# motor_driver.net
KiCad netlist of a schematic drawn in EAGLE
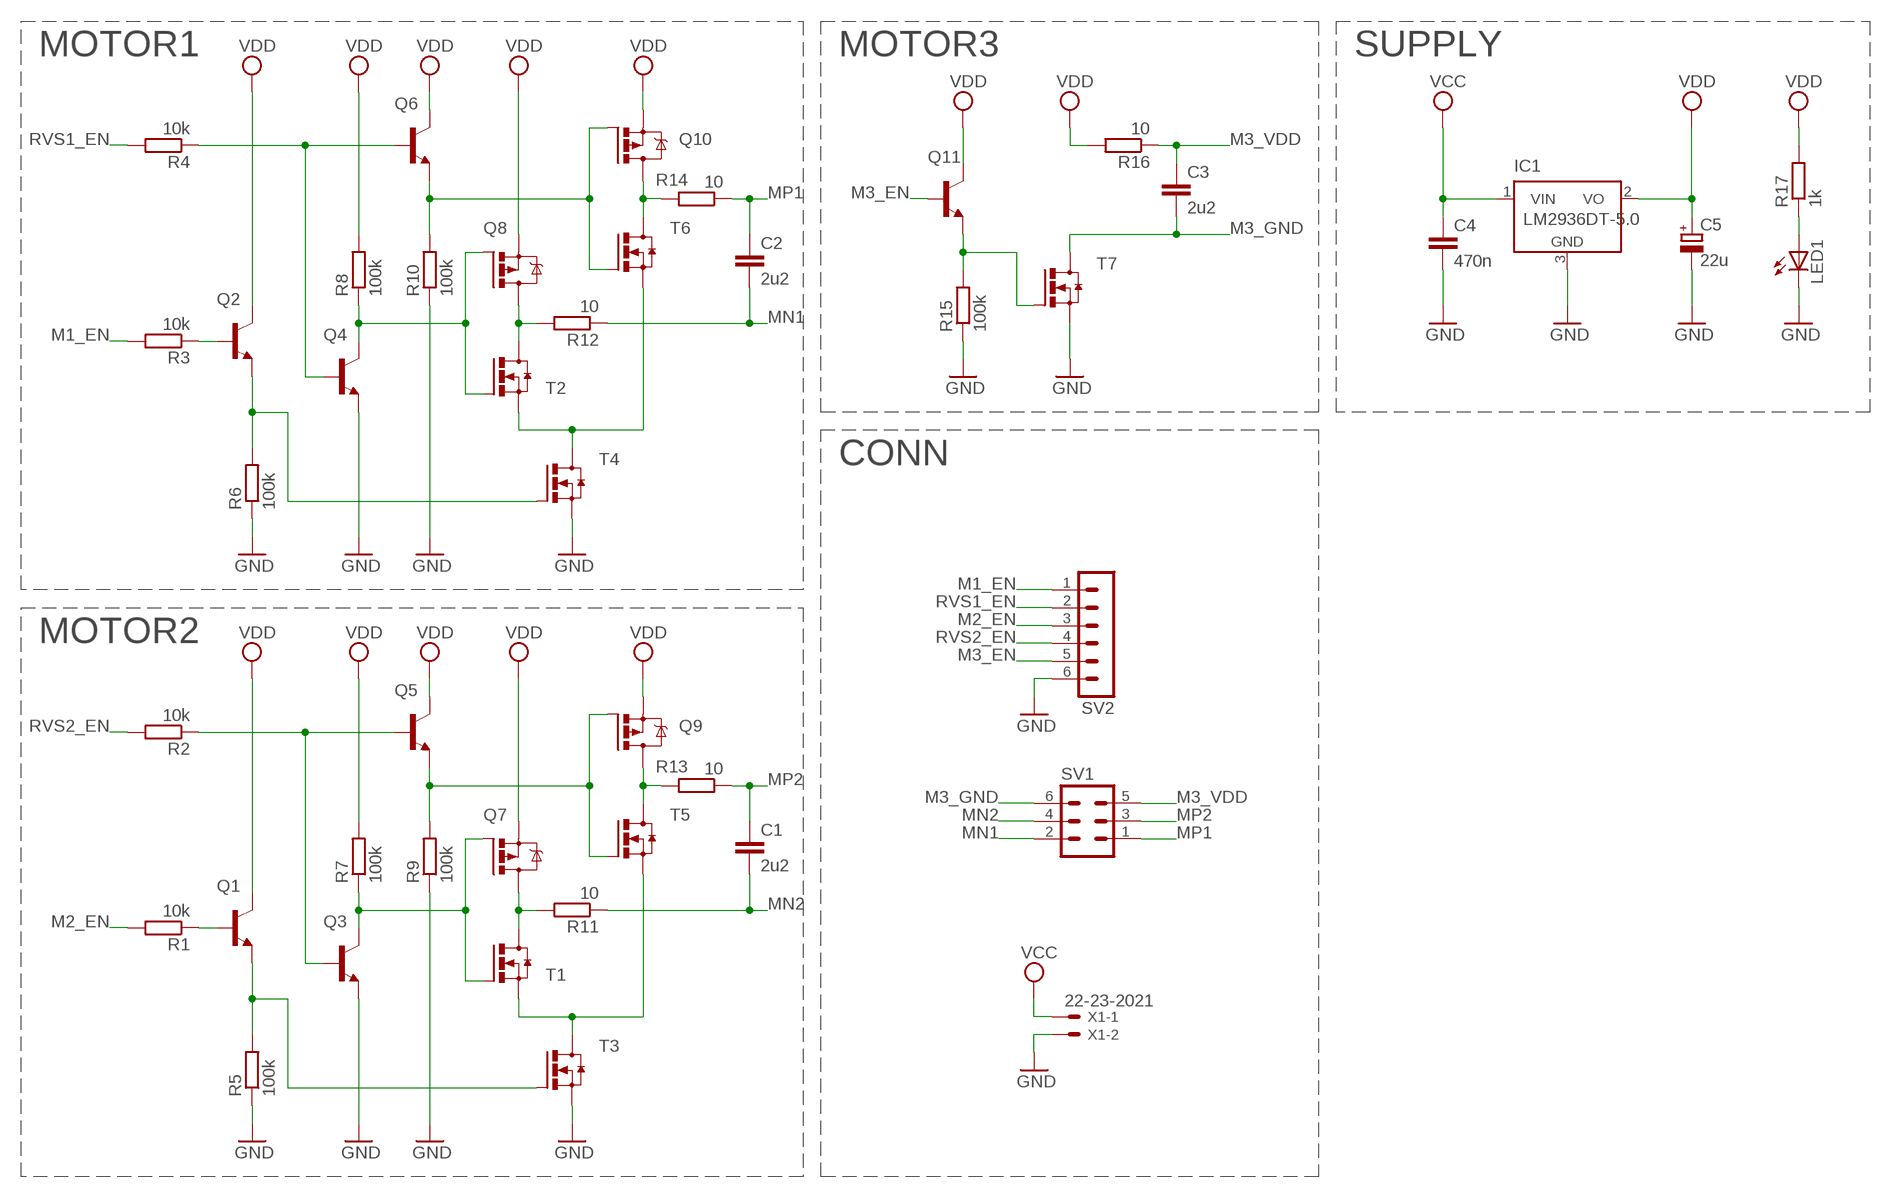
[diagram p0: schematic, sheet 1]

(export (version "E")
  (design (tool "Eeschema 10.0.6"))
  (components
    (comp (ref "C1")
      (value "2u2")
      (footprint "eagle-import:C025-025X050")
      (libsource (lib "eagle-import") (part "C-EU025-025X050"))
    )
    (comp (ref "C2")
      (value "2u2")
      (footprint "eagle-import:C025-025X050")
      (libsource (lib "eagle-import") (part "C-EU025-025X050"))
    )
    (comp (ref "C3")
      (value "2u2")
      (footprint "eagle-import:C025-025X050")
      (libsource (lib "eagle-import") (part "C-EU025-025X050"))
    )
    (comp (ref "C4")
      (value "470n")
      (footprint "eagle-import:C0805")
      (libsource (lib "eagle-import") (part "C-EUC0805"))
    )
    (comp (ref "C5")
      (value "22u")
      (footprint "eagle-import:150CLZ-1014")
      (libsource (lib "eagle-import") (part "CPOL-EU150CLZ-1014"))
    )
    (comp (ref "IC1")
      (value "LM2936DT-5.0")
      (footprint "eagle-import:TO252")
      (fields (field (name "MF") "NATIONAL SEMICONDUCTOR") (field (name "MPN") "LM2936DT-5.0/NOPB"))
      (libsource (lib "eagle-import") (part "LM2936?DT-5.0"))
    )
    (comp (ref "LED1")
      (value "LEDCHIPLED_0603")
      (footprint "eagle-import:CHIPLED_0603")
      (libsource (lib "eagle-import") (part "LEDCHIPLED_0603"))
    )
    (comp (ref "Q1")
      (value "BC849SMD")
      (footprint "eagle-import:SOT23-BEC")
      (libsource (lib "eagle-import") (part "BC849SMD"))
    )
    (comp (ref "Q2")
      (value "BC849SMD")
      (footprint "eagle-import:SOT23-BEC")
      (libsource (lib "eagle-import") (part "BC849SMD"))
    )
    (comp (ref "Q3")
      (value "BC849SMD")
      (footprint "eagle-import:SOT23-BEC")
      (libsource (lib "eagle-import") (part "BC849SMD"))
    )
    (comp (ref "Q4")
      (value "BC849SMD")
      (footprint "eagle-import:SOT23-BEC")
      (libsource (lib "eagle-import") (part "BC849SMD"))
    )
    (comp (ref "Q5")
      (value "BC849SMD")
      (footprint "eagle-import:SOT23-BEC")
      (libsource (lib "eagle-import") (part "BC849SMD"))
    )
    (comp (ref "Q6")
      (value "BC849SMD")
      (footprint "eagle-import:SOT23-BEC")
      (libsource (lib "eagle-import") (part "BC849SMD"))
    )
    (comp (ref "Q7")
      (value "IRLML5203")
      (footprint "eagle-import:MICRO3")
      (libsource (lib "eagle-import") (part "IRLML5203"))
    )
    (comp (ref "Q8")
      (value "IRLML5203")
      (footprint "eagle-import:MICRO3")
      (libsource (lib "eagle-import") (part "IRLML5203"))
    )
    (comp (ref "Q9")
      (value "IRLML5203")
      (footprint "eagle-import:MICRO3")
      (libsource (lib "eagle-import") (part "IRLML5203"))
    )
    (comp (ref "Q10")
      (value "IRLML5203")
      (footprint "eagle-import:MICRO3")
      (libsource (lib "eagle-import") (part "IRLML5203"))
    )
    (comp (ref "Q11")
      (value "BC849SMD")
      (footprint "eagle-import:SOT23-BEC")
      (libsource (lib "eagle-import") (part "BC849SMD"))
    )
    (comp (ref "R1")
      (value "10k")
      (footprint "eagle-import:R0603")
      (libsource (lib "eagle-import") (part "R-EU_R0603"))
    )
    (comp (ref "R2")
      (value "10k")
      (footprint "eagle-import:R0603")
      (libsource (lib "eagle-import") (part "R-EU_R0603"))
    )
    (comp (ref "R3")
      (value "10k")
      (footprint "eagle-import:R0603")
      (libsource (lib "eagle-import") (part "R-EU_R0603"))
    )
    (comp (ref "R4")
      (value "10k")
      (footprint "eagle-import:R0603")
      (libsource (lib "eagle-import") (part "R-EU_R0603"))
    )
    (comp (ref "R5")
      (value "100k")
      (footprint "eagle-import:R0603")
      (libsource (lib "eagle-import") (part "R-EU_R0603"))
    )
    (comp (ref "R6")
      (value "100k")
      (footprint "eagle-import:R0603")
      (libsource (lib "eagle-import") (part "R-EU_R0603"))
    )
    (comp (ref "R7")
      (value "100k")
      (footprint "eagle-import:R0603")
      (libsource (lib "eagle-import") (part "R-EU_R0603"))
    )
    (comp (ref "R8")
      (value "100k")
      (footprint "eagle-import:R0603")
      (libsource (lib "eagle-import") (part "R-EU_R0603"))
    )
    (comp (ref "R9")
      (value "100k")
      (footprint "eagle-import:R0603")
      (libsource (lib "eagle-import") (part "R-EU_R0603"))
    )
    (comp (ref "R10")
      (value "100k")
      (footprint "eagle-import:R0603")
      (libsource (lib "eagle-import") (part "R-EU_R0603"))
    )
    (comp (ref "R11")
      (value "10")
      (footprint "eagle-import:R2512")
      (libsource (lib "eagle-import") (part "R-EU_R2512"))
    )
    (comp (ref "R12")
      (value "10")
      (footprint "eagle-import:R2512")
      (libsource (lib "eagle-import") (part "R-EU_R2512"))
    )
    (comp (ref "R13")
      (value "10")
      (footprint "eagle-import:R2512")
      (libsource (lib "eagle-import") (part "R-EU_R2512"))
    )
    (comp (ref "R14")
      (value "10")
      (footprint "eagle-import:R2512")
      (libsource (lib "eagle-import") (part "R-EU_R2512"))
    )
    (comp (ref "R15")
      (value "100k")
      (footprint "eagle-import:R0603")
      (libsource (lib "eagle-import") (part "R-EU_R0603"))
    )
    (comp (ref "R16")
      (value "10")
      (footprint "eagle-import:R0603")
      (libsource (lib "eagle-import") (part "R-EU_R0603"))
    )
    (comp (ref "R17")
      (value "1k")
      (footprint "eagle-import:R0603")
      (libsource (lib "eagle-import") (part "R-EU_R0603"))
    )
    (comp (ref "SV1")
      (value "MA03-2")
      (footprint "eagle-import:MA03-2")
      (libsource (lib "eagle-import") (part "MA03-2"))
    )
    (comp (ref "SV2")
      (value "MA06-1")
      (footprint "eagle-import:MA06-1")
      (libsource (lib "eagle-import") (part "MA06-1"))
    )
    (comp (ref "T1")
      (value "IRLML2803")
      (footprint "eagle-import:MICRO3")
      (libsource (lib "eagle-import") (part "IRLML2803"))
    )
    (comp (ref "T2")
      (value "IRLML2803")
      (footprint "eagle-import:MICRO3")
      (libsource (lib "eagle-import") (part "IRLML2803"))
    )
    (comp (ref "T3")
      (value "IRLML2803")
      (footprint "eagle-import:MICRO3")
      (libsource (lib "eagle-import") (part "IRLML2803"))
    )
    (comp (ref "T4")
      (value "IRLML2803")
      (footprint "eagle-import:MICRO3")
      (libsource (lib "eagle-import") (part "IRLML2803"))
    )
    (comp (ref "T5")
      (value "IRLML2803")
      (footprint "eagle-import:MICRO3")
      (libsource (lib "eagle-import") (part "IRLML2803"))
    )
    (comp (ref "T6")
      (value "IRLML2803")
      (footprint "eagle-import:MICRO3")
      (libsource (lib "eagle-import") (part "IRLML2803"))
    )
    (comp (ref "T7")
      (value "IRLML2803")
      (footprint "eagle-import:MICRO3")
      (libsource (lib "eagle-import") (part "IRLML2803"))
    )
    (comp (ref "X1")
      (value "22-23-2021")
      (footprint "eagle-import:22-23-2021")
      (fields (field (name "MF") "MOLEX"))
      (libsource (lib "eagle-import") (part "22-23-2021"))
    )
  )
  (nets
    (net (code "1") (name "/M1_EN") (class "Default")
      (node (ref "R3") (pin "2") (pinfunction "2_2") (pintype "passive"))
      (node (ref "SV2") (pin "1") (pinfunction "1_1") (pintype "passive"))
    )
    (net (code "2") (name "/M2_EN") (class "Default")
      (node (ref "R1") (pin "2") (pinfunction "2_2") (pintype "passive"))
      (node (ref "SV2") (pin "3") (pinfunction "3_3") (pintype "passive"))
    )
    (net (code "3") (name "/M3_EN") (class "Default")
      (node (ref "Q11") (pin "B") (pinfunction "B_B") (pintype "passive"))
      (node (ref "SV2") (pin "5") (pinfunction "5_5") (pintype "passive"))
    )
    (net (code "4") (name "/M3_GND") (class "Default")
      (node (ref "C3") (pin "2") (pinfunction "2_2") (pintype "passive"))
      (node (ref "SV1") (pin "6") (pinfunction "6_6") (pintype "passive"))
      (node (ref "T7") (pin "3") (pinfunction "D_3") (pintype "passive"))
    )
    (net (code "5") (name "/M3_VDD") (class "Default")
      (node (ref "C3") (pin "1") (pinfunction "1_1") (pintype "passive"))
      (node (ref "R16") (pin "1") (pinfunction "1_1") (pintype "passive"))
      (node (ref "SV1") (pin "5") (pinfunction "5_5") (pintype "passive"))
    )
    (net (code "6") (name "/MN1") (class "Default")
      (node (ref "C2") (pin "2") (pinfunction "2_2") (pintype "passive"))
      (node (ref "R12") (pin "1") (pinfunction "1_1") (pintype "passive"))
      (node (ref "SV1") (pin "2") (pinfunction "2_2") (pintype "passive"))
    )
    (net (code "7") (name "/MN2") (class "Default")
      (node (ref "C1") (pin "2") (pinfunction "2_2") (pintype "passive"))
      (node (ref "R11") (pin "1") (pinfunction "1_1") (pintype "passive"))
      (node (ref "SV1") (pin "4") (pinfunction "4_4") (pintype "passive"))
    )
    (net (code "8") (name "/MP1") (class "Default")
      (node (ref "C2") (pin "1") (pinfunction "1_1") (pintype "passive"))
      (node (ref "R14") (pin "1") (pinfunction "1_1") (pintype "passive"))
      (node (ref "SV1") (pin "1") (pinfunction "1_1") (pintype "passive"))
    )
    (net (code "9") (name "/MP2") (class "Default")
      (node (ref "C1") (pin "1") (pinfunction "1_1") (pintype "passive"))
      (node (ref "R13") (pin "1") (pinfunction "1_1") (pintype "passive"))
      (node (ref "SV1") (pin "3") (pinfunction "3_3") (pintype "passive"))
    )
    (net (code "10") (name "/RVS1_EN") (class "Default")
      (node (ref "R4") (pin "2") (pinfunction "2_2") (pintype "passive"))
      (node (ref "SV2") (pin "2") (pinfunction "2_2") (pintype "passive"))
    )
    (net (code "11") (name "/RVS2_EN") (class "Default")
      (node (ref "R2") (pin "2") (pinfunction "2_2") (pintype "passive"))
      (node (ref "SV2") (pin "4") (pinfunction "4_4") (pintype "passive"))
    )
    (net (code "12") (name "GND") (class "Default")
      (node (ref "C4") (pin "2") (pinfunction "2_2") (pintype "passive"))
      (node (ref "C5") (pin "-") (pinfunction "-_-") (pintype "passive"))
      (node (ref "IC1") (pin "3") (pinfunction "GND_3") (pintype "passive"))
      (node (ref "LED1") (pin "C") (pinfunction "C_C") (pintype "passive"))
      (node (ref "Q3") (pin "E") (pinfunction "E_E") (pintype "passive"))
      (node (ref "Q4") (pin "E") (pinfunction "E_E") (pintype "passive"))
      (node (ref "R10") (pin "1") (pinfunction "1_1") (pintype "passive"))
      (node (ref "R15") (pin "1") (pinfunction "1_1") (pintype "passive"))
      (node (ref "R5") (pin "1") (pinfunction "1_1") (pintype "passive"))
      (node (ref "R6") (pin "1") (pinfunction "1_1") (pintype "passive"))
      (node (ref "R9") (pin "1") (pinfunction "1_1") (pintype "passive"))
      (node (ref "SV2") (pin "6") (pinfunction "6_6") (pintype "passive"))
      (node (ref "T3") (pin "2") (pinfunction "S_2") (pintype "passive"))
      (node (ref "T4") (pin "2") (pinfunction "S_2") (pintype "passive"))
      (node (ref "T7") (pin "2") (pinfunction "S_2") (pintype "passive"))
      (node (ref "X1") (pin "2") (pinfunction "S_2") (pintype "passive"))
    )
    (net (code "13") (name "Net-(LED1-PadA)") (class "Default")
      (node (ref "LED1") (pin "A") (pinfunction "A_A") (pintype "passive"))
      (node (ref "R17") (pin "1") (pinfunction "1_1") (pintype "passive"))
    )
    (net (code "14") (name "Net-(Q1-PadB)") (class "Default")
      (node (ref "Q1") (pin "B") (pinfunction "B_B") (pintype "passive"))
      (node (ref "R1") (pin "1") (pinfunction "1_1") (pintype "passive"))
    )
    (net (code "15") (name "Net-(Q2-PadB)") (class "Default")
      (node (ref "Q2") (pin "B") (pinfunction "B_B") (pintype "passive"))
      (node (ref "R3") (pin "1") (pinfunction "1_1") (pintype "passive"))
    )
    (net (code "16") (name "Net-(Q3-PadB)") (class "Default")
      (node (ref "Q3") (pin "B") (pinfunction "B_B") (pintype "passive"))
      (node (ref "Q5") (pin "B") (pinfunction "B_B") (pintype "passive"))
      (node (ref "R2") (pin "1") (pinfunction "1_1") (pintype "passive"))
    )
    (net (code "17") (name "Net-(Q4-PadB)") (class "Default")
      (node (ref "Q4") (pin "B") (pinfunction "B_B") (pintype "passive"))
      (node (ref "Q6") (pin "B") (pinfunction "B_B") (pintype "passive"))
      (node (ref "R4") (pin "1") (pinfunction "1_1") (pintype "passive"))
    )
    (net (code "18") (name "Net-(Q7-D)") (class "Default")
      (node (ref "Q7") (pin "3") (pinfunction "D_3") (pintype "passive"))
      (node (ref "R11") (pin "2") (pinfunction "2_2") (pintype "passive"))
      (node (ref "T1") (pin "3") (pinfunction "D_3") (pintype "passive"))
    )
    (net (code "19") (name "Net-(Q7-G)") (class "Default")
      (node (ref "Q3") (pin "C") (pinfunction "C_C") (pintype "passive"))
      (node (ref "Q7") (pin "1") (pinfunction "G_1") (pintype "passive"))
      (node (ref "R7") (pin "1") (pinfunction "1_1") (pintype "passive"))
      (node (ref "T1") (pin "1") (pinfunction "G_1") (pintype "passive"))
    )
    (net (code "20") (name "Net-(Q8-D)") (class "Default")
      (node (ref "Q8") (pin "3") (pinfunction "D_3") (pintype "passive"))
      (node (ref "R12") (pin "2") (pinfunction "2_2") (pintype "passive"))
      (node (ref "T2") (pin "3") (pinfunction "D_3") (pintype "passive"))
    )
    (net (code "21") (name "Net-(Q8-G)") (class "Default")
      (node (ref "Q4") (pin "C") (pinfunction "C_C") (pintype "passive"))
      (node (ref "Q8") (pin "1") (pinfunction "G_1") (pintype "passive"))
      (node (ref "R8") (pin "1") (pinfunction "1_1") (pintype "passive"))
      (node (ref "T2") (pin "1") (pinfunction "G_1") (pintype "passive"))
    )
    (net (code "22") (name "Net-(Q9-D)") (class "Default")
      (node (ref "Q9") (pin "3") (pinfunction "D_3") (pintype "passive"))
      (node (ref "R13") (pin "2") (pinfunction "2_2") (pintype "passive"))
      (node (ref "T5") (pin "3") (pinfunction "D_3") (pintype "passive"))
    )
    (net (code "23") (name "Net-(Q9-G)") (class "Default")
      (node (ref "Q5") (pin "E") (pinfunction "E_E") (pintype "passive"))
      (node (ref "Q9") (pin "1") (pinfunction "G_1") (pintype "passive"))
      (node (ref "R9") (pin "2") (pinfunction "2_2") (pintype "passive"))
      (node (ref "T5") (pin "1") (pinfunction "G_1") (pintype "passive"))
    )
    (net (code "24") (name "Net-(Q10-D)") (class "Default")
      (node (ref "Q10") (pin "3") (pinfunction "D_3") (pintype "passive"))
      (node (ref "R14") (pin "2") (pinfunction "2_2") (pintype "passive"))
      (node (ref "T6") (pin "3") (pinfunction "D_3") (pintype "passive"))
    )
    (net (code "25") (name "Net-(Q10-G)") (class "Default")
      (node (ref "Q10") (pin "1") (pinfunction "G_1") (pintype "passive"))
      (node (ref "Q6") (pin "E") (pinfunction "E_E") (pintype "passive"))
      (node (ref "R10") (pin "2") (pinfunction "2_2") (pintype "passive"))
      (node (ref "T6") (pin "1") (pinfunction "G_1") (pintype "passive"))
    )
    (net (code "26") (name "Net-(T1-S)") (class "Default")
      (node (ref "T1") (pin "2") (pinfunction "S_2") (pintype "passive"))
      (node (ref "T3") (pin "3") (pinfunction "D_3") (pintype "passive"))
      (node (ref "T5") (pin "2") (pinfunction "S_2") (pintype "passive"))
    )
    (net (code "27") (name "Net-(T2-S)") (class "Default")
      (node (ref "T2") (pin "2") (pinfunction "S_2") (pintype "passive"))
      (node (ref "T4") (pin "3") (pinfunction "D_3") (pintype "passive"))
      (node (ref "T6") (pin "2") (pinfunction "S_2") (pintype "passive"))
    )
    (net (code "28") (name "Net-(T3-G)") (class "Default")
      (node (ref "Q1") (pin "E") (pinfunction "E_E") (pintype "passive"))
      (node (ref "R5") (pin "2") (pinfunction "2_2") (pintype "passive"))
      (node (ref "T3") (pin "1") (pinfunction "G_1") (pintype "passive"))
    )
    (net (code "29") (name "Net-(T4-G)") (class "Default")
      (node (ref "Q2") (pin "E") (pinfunction "E_E") (pintype "passive"))
      (node (ref "R6") (pin "2") (pinfunction "2_2") (pintype "passive"))
      (node (ref "T4") (pin "1") (pinfunction "G_1") (pintype "passive"))
    )
    (net (code "30") (name "Net-(T7-G)") (class "Default")
      (node (ref "Q11") (pin "E") (pinfunction "E_E") (pintype "passive"))
      (node (ref "R15") (pin "2") (pinfunction "2_2") (pintype "passive"))
      (node (ref "T7") (pin "1") (pinfunction "G_1") (pintype "passive"))
    )
    (net (code "31") (name "VCC") (class "Default")
      (node (ref "C4") (pin "1") (pinfunction "1_1") (pintype "passive"))
      (node (ref "IC1") (pin "1") (pinfunction "VIN_1") (pintype "input"))
      (node (ref "X1") (pin "1") (pinfunction "S_1") (pintype "passive"))
    )
    (net (code "32") (name "VDD") (class "Default")
      (node (ref "C5") (pin "+") (pinfunction "+_+") (pintype "passive"))
      (node (ref "IC1") (pin "2") (pinfunction "VO_2") (pintype "passive"))
      (node (ref "Q1") (pin "C") (pinfunction "C_C") (pintype "passive"))
      (node (ref "Q10") (pin "2") (pinfunction "S_2") (pintype "passive"))
      (node (ref "Q11") (pin "C") (pinfunction "C_C") (pintype "passive"))
      (node (ref "Q2") (pin "C") (pinfunction "C_C") (pintype "passive"))
      (node (ref "Q5") (pin "C") (pinfunction "C_C") (pintype "passive"))
      (node (ref "Q6") (pin "C") (pinfunction "C_C") (pintype "passive"))
      (node (ref "Q7") (pin "2") (pinfunction "S_2") (pintype "passive"))
      (node (ref "Q8") (pin "2") (pinfunction "S_2") (pintype "passive"))
      (node (ref "Q9") (pin "2") (pinfunction "S_2") (pintype "passive"))
      (node (ref "R16") (pin "2") (pinfunction "2_2") (pintype "passive"))
      (node (ref "R17") (pin "2") (pinfunction "2_2") (pintype "passive"))
      (node (ref "R7") (pin "2") (pinfunction "2_2") (pintype "passive"))
      (node (ref "R8") (pin "2") (pinfunction "2_2") (pintype "passive"))
    )
  )
)
